# Board_Schematic1.net
KiCad netlist of a schematic drawn in EAGLE
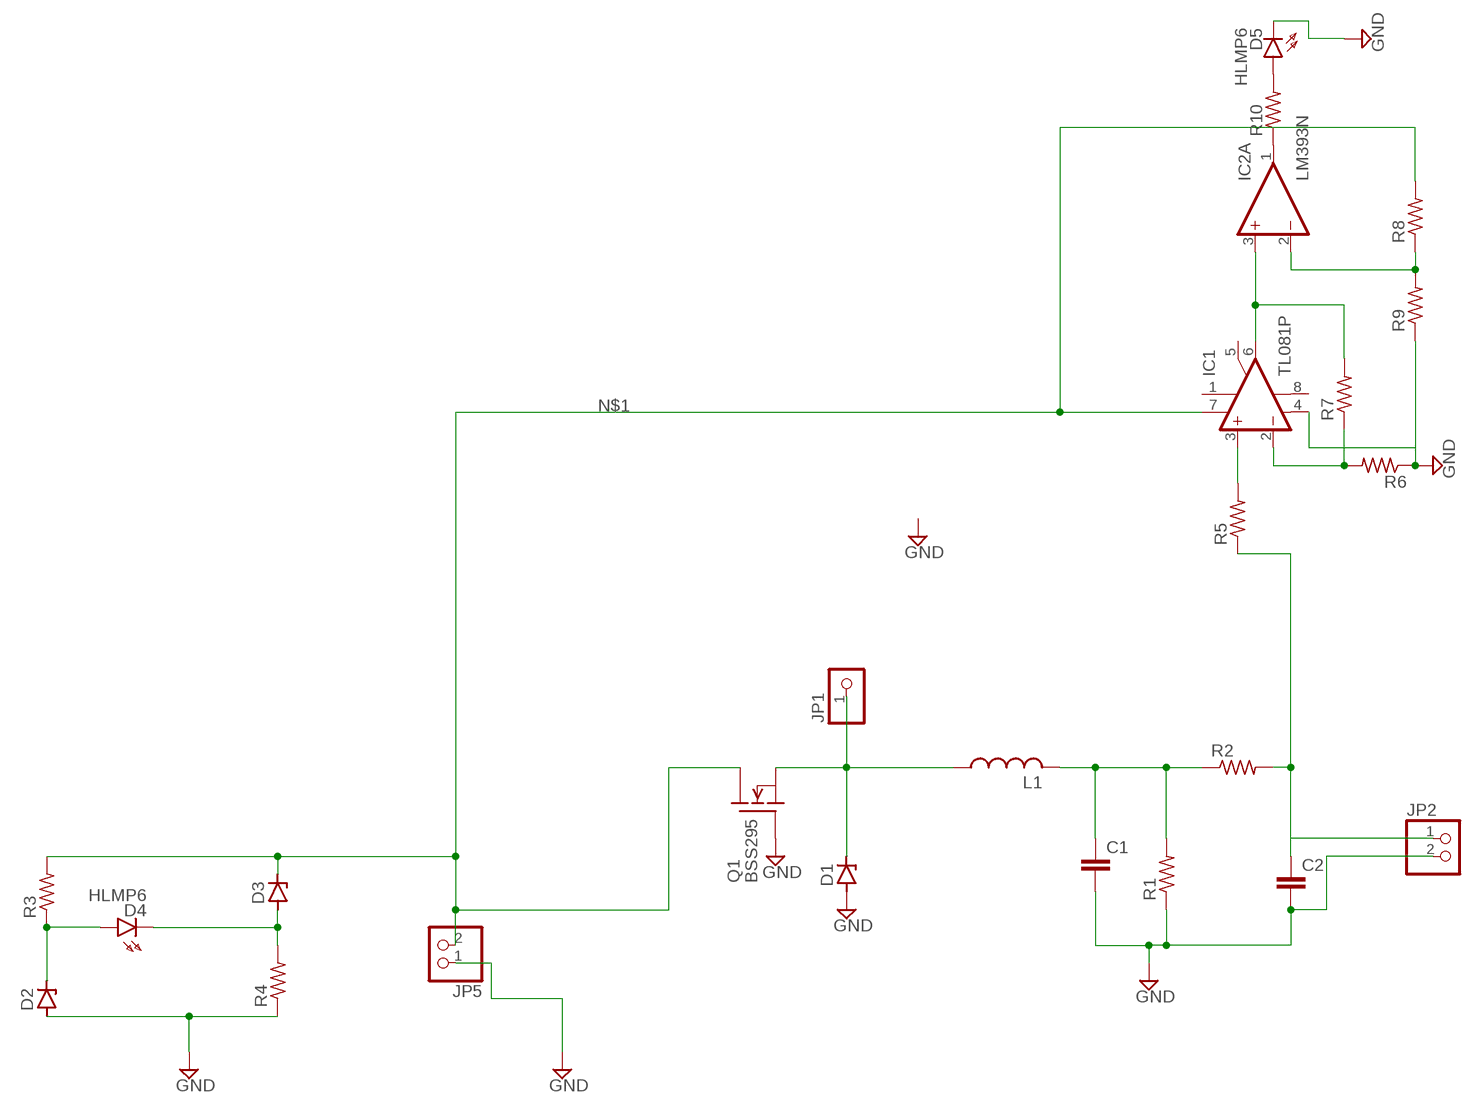
[diagram p0: schematic, sheet 1]

(export (version "E")
  (design (tool "Eeschema 10.0.6"))
  (components
    (comp (ref "C1")
      (value "C-EU025-025X050")
      (footprint "eagle-import:C025-025X050")
      (libsource (lib "eagle-import") (part "C-EU025-025X050"))
    )
    (comp (ref "C2")
      (value "C-EU025-025X050")
      (footprint "eagle-import:C025-025X050")
      (libsource (lib "eagle-import") (part "C-EU025-025X050"))
    )
    (comp (ref "D1")
      (value "ZENER-DIODEDO35Z10")
      (footprint "eagle-import:DO35Z10")
      (libsource (lib "eagle-import") (part "ZENER-DIODEDO35Z10"))
    )
    (comp (ref "D2")
      (value "ZENER-DIODEDO35Z10")
      (footprint "eagle-import:DO35Z10")
      (libsource (lib "eagle-import") (part "ZENER-DIODEDO35Z10"))
    )
    (comp (ref "D3")
      (value "ZENER-DIODEDO35Z10")
      (footprint "eagle-import:DO35Z10")
      (libsource (lib "eagle-import") (part "ZENER-DIODEDO35Z10"))
    )
    (comp (ref "D4")
      (value "HLMP6")
      (footprint "eagle-import:HLMP6")
      (fields (field (name "MF") "AGILENT TECHNOLOGIES") (field (name "MPN") "HLMP-6500"))
      (libsource (lib "eagle-import") (part "HLMP6"))
    )
    (comp (ref "D5")
      (value "HLMP6")
      (footprint "eagle-import:HLMP6")
      (fields (field (name "MF") "AGILENT TECHNOLOGIES") (field (name "MPN") "HLMP-6500"))
      (libsource (lib "eagle-import") (part "HLMP6"))
    )
    (comp (ref "IC1")
      (value "TL081P")
      (footprint "eagle-import:DIL08")
      (libsource (lib "eagle-import") (part "TL081P"))
    )
    (comp (ref "IC2")
      (value "LM393N")
      (footprint "eagle-import:DIL08")
      (libsource (lib "eagle-import") (part "LM393N"))
    )
    (comp (ref "JP1")
      (value "PINHD-1X1")
      (footprint "eagle-import:1X01")
      (libsource (lib "eagle-import") (part "PINHD-1X1"))
    )
    (comp (ref "JP2")
      (value "PINHD-1X2")
      (footprint "eagle-import:1X02")
      (libsource (lib "eagle-import") (part "PINHD-1X2"))
    )
    (comp (ref "JP5")
      (value "PINHD-1X2")
      (footprint "eagle-import:1X02")
      (libsource (lib "eagle-import") (part "PINHD-1X2"))
    )
    (comp (ref "L1")
      (value "L-US6000-XXX-RC")
      (footprint "eagle-import:6000-XXXX-RC")
      (libsource (lib "eagle-import") (part "L-US6000-XXX-RC"))
    )
    (comp (ref "Q1")
      (value "BSS295")
      (footprint "eagle-import:TO92")
      (libsource (lib "eagle-import") (part "BSS295"))
    )
    (comp (ref "R1")
      (value "R-US_0204/7")
      (footprint "eagle-import:0204_7")
      (libsource (lib "eagle-import") (part "R-US_0204/7"))
    )
    (comp (ref "R2")
      (value "R-US_0204/7")
      (footprint "eagle-import:0204_7")
      (libsource (lib "eagle-import") (part "R-US_0204/7"))
    )
    (comp (ref "R3")
      (value "R-US_0204/7")
      (footprint "eagle-import:0204_7")
      (libsource (lib "eagle-import") (part "R-US_0204/7"))
    )
    (comp (ref "R4")
      (value "R-US_0204/7")
      (footprint "eagle-import:0204_7")
      (libsource (lib "eagle-import") (part "R-US_0204/7"))
    )
    (comp (ref "R5")
      (value "R-US_0204/7")
      (footprint "eagle-import:0204_7")
      (libsource (lib "eagle-import") (part "R-US_0204/7"))
    )
    (comp (ref "R6")
      (value "R-US_0204/7")
      (footprint "eagle-import:0204_7")
      (libsource (lib "eagle-import") (part "R-US_0204/7"))
    )
    (comp (ref "R7")
      (value "R-US_0204/7")
      (footprint "eagle-import:0204_7")
      (libsource (lib "eagle-import") (part "R-US_0204/7"))
    )
    (comp (ref "R8")
      (value "R-US_0204/7")
      (footprint "eagle-import:0204_7")
      (libsource (lib "eagle-import") (part "R-US_0204/7"))
    )
    (comp (ref "R9")
      (value "R-US_0204/7")
      (footprint "eagle-import:0204_7")
      (libsource (lib "eagle-import") (part "R-US_0204/7"))
    )
    (comp (ref "R10")
      (value "R-US_0204/7")
      (footprint "eagle-import:0204_7")
      (libsource (lib "eagle-import") (part "R-US_0204/7"))
    )
  )
  (nets
    (net (code "1") (name "/N$1") (class "Default")
      (node (ref "D3") (pin "C") (pinfunction "C_C") (pintype "passive"))
      (node (ref "IC1") (pin "7") (pinfunction "V+_7") (pintype "power_in"))
      (node (ref "JP5") (pin "2") (pinfunction "2_2") (pintype "passive"))
      (node (ref "Q1") (pin "2") (pinfunction "D_2") (pintype "passive"))
      (node (ref "R3") (pin "2") (pinfunction "2_2") (pintype "passive"))
      (node (ref "R8") (pin "2") (pinfunction "2_2") (pintype "passive"))
    )
    (net (code "2") (name "GND") (class "Default")
      (node (ref "C1") (pin "2") (pinfunction "2_2") (pintype "passive"))
      (node (ref "C2") (pin "2") (pinfunction "2_2") (pintype "passive"))
      (node (ref "D1") (pin "A") (pinfunction "A_A") (pintype "passive"))
      (node (ref "D2") (pin "A") (pinfunction "A_A") (pintype "passive"))
      (node (ref "D5") (pin "K") (pinfunction "K_K") (pintype "passive"))
      (node (ref "IC1") (pin "4") (pinfunction "V-_4") (pintype "power_in"))
      (node (ref "JP2") (pin "2") (pinfunction "2_2") (pintype "passive"))
      (node (ref "JP5") (pin "1") (pinfunction "1_1") (pintype "passive"))
      (node (ref "Q1") (pin "1") (pinfunction "G_1") (pintype "passive"))
      (node (ref "R1") (pin "1") (pinfunction "1_1") (pintype "passive"))
      (node (ref "R4") (pin "1") (pinfunction "1_1") (pintype "passive"))
      (node (ref "R6") (pin "1") (pinfunction "1_1") (pintype "passive"))
      (node (ref "R9") (pin "1") (pinfunction "1_1") (pintype "passive"))
    )
    (net (code "3") (name "Net-(C1-Pad1)") (class "Default")
      (node (ref "C1") (pin "1") (pinfunction "1_1") (pintype "passive"))
      (node (ref "L1") (pin "2") (pinfunction "2_2") (pintype "passive"))
      (node (ref "R1") (pin "2") (pinfunction "2_2") (pintype "passive"))
      (node (ref "R2") (pin "1") (pinfunction "1_1") (pintype "passive"))
    )
    (net (code "4") (name "Net-(C2-Pad1)") (class "Default")
      (node (ref "C2") (pin "1") (pinfunction "1_1") (pintype "passive"))
      (node (ref "JP2") (pin "1") (pinfunction "1_1") (pintype "passive"))
      (node (ref "R2") (pin "2") (pinfunction "2_2") (pintype "passive"))
      (node (ref "R5") (pin "1") (pinfunction "1_1") (pintype "passive"))
    )
    (net (code "5") (name "Net-(D2-PadC)") (class "Default")
      (node (ref "D2") (pin "C") (pinfunction "C_C") (pintype "passive"))
      (node (ref "D4") (pin "A") (pinfunction "A_A") (pintype "passive"))
      (node (ref "R3") (pin "1") (pinfunction "1_1") (pintype "passive"))
    )
    (net (code "6") (name "Net-(D3-PadA)") (class "Default")
      (node (ref "D3") (pin "A") (pinfunction "A_A") (pintype "passive"))
      (node (ref "D4") (pin "K") (pinfunction "K_K") (pintype "passive"))
      (node (ref "R4") (pin "2") (pinfunction "2_2") (pintype "passive"))
    )
    (net (code "7") (name "Net-(D5-PadA)") (class "Default")
      (node (ref "D5") (pin "A") (pinfunction "A_A") (pintype "passive"))
      (node (ref "R10") (pin "2") (pinfunction "2_2") (pintype "passive"))
    )
    (net (code "8") (name "Net-(IC1-+IN)") (class "Default")
      (node (ref "IC1") (pin "3") (pinfunction "+IN_3") (pintype "input"))
      (node (ref "R5") (pin "2") (pinfunction "2_2") (pintype "passive"))
    )
    (net (code "9") (name "Net-(IC1--IN)") (class "Default")
      (node (ref "IC1") (pin "2") (pinfunction "-IN_2") (pintype "input"))
      (node (ref "R6") (pin "2") (pinfunction "2_2") (pintype "passive"))
      (node (ref "R7") (pin "1") (pinfunction "1_1") (pintype "passive"))
    )
    (net (code "10") (name "Net-(IC1-OUT)") (class "Default")
      (node (ref "IC1") (pin "6") (pinfunction "OUT_6") (pintype "output"))
      (node (ref "IC2") (pin "3") (pinfunction "+IN_3") (pintype "input"))
      (node (ref "R7") (pin "2") (pinfunction "2_2") (pintype "passive"))
    )
    (net (code "11") (name "Net-(IC2A--IN)") (class "Default")
      (node (ref "IC2") (pin "2") (pinfunction "-IN_2") (pintype "input"))
      (node (ref "R8") (pin "1") (pinfunction "1_1") (pintype "passive"))
      (node (ref "R9") (pin "2") (pinfunction "2_2") (pintype "passive"))
    )
    (net (code "12") (name "Net-(IC2A-OUT)") (class "Default")
      (node (ref "IC2") (pin "1") (pinfunction "OUT_1") (pintype "output"))
      (node (ref "R10") (pin "1") (pinfunction "1_1") (pintype "passive"))
    )
    (net (code "13") (name "Net-(Q1-S)") (class "Default")
      (node (ref "D1") (pin "C") (pinfunction "C_C") (pintype "passive"))
      (node (ref "JP1") (pin "1") (pinfunction "1_1") (pintype "passive"))
      (node (ref "L1") (pin "1") (pinfunction "1_1") (pintype "passive"))
      (node (ref "Q1") (pin "3") (pinfunction "S_3") (pintype "passive"))
    )
    (net (code "14") (name "unconnected-(IC1-ON1-Pad1)") (class "Default")
      (node (ref "IC1") (pin "1") (pinfunction "ON1_1") (pintype "passive"))
    )
    (net (code "15") (name "unconnected-(IC1-ON2-Pad5)") (class "Default")
      (node (ref "IC1") (pin "5") (pinfunction "ON2_5") (pintype "passive"))
    )
    (net (code "16") (name "unconnected-(IC1-OPT-Pad8)") (class "Default")
      (node (ref "IC1") (pin "8") (pinfunction "OPT_8") (pintype "passive"))
    )
  )
)
